# PWM_CONTROLLER.net
KiCad netlist of a schematic drawn in Altium Designer
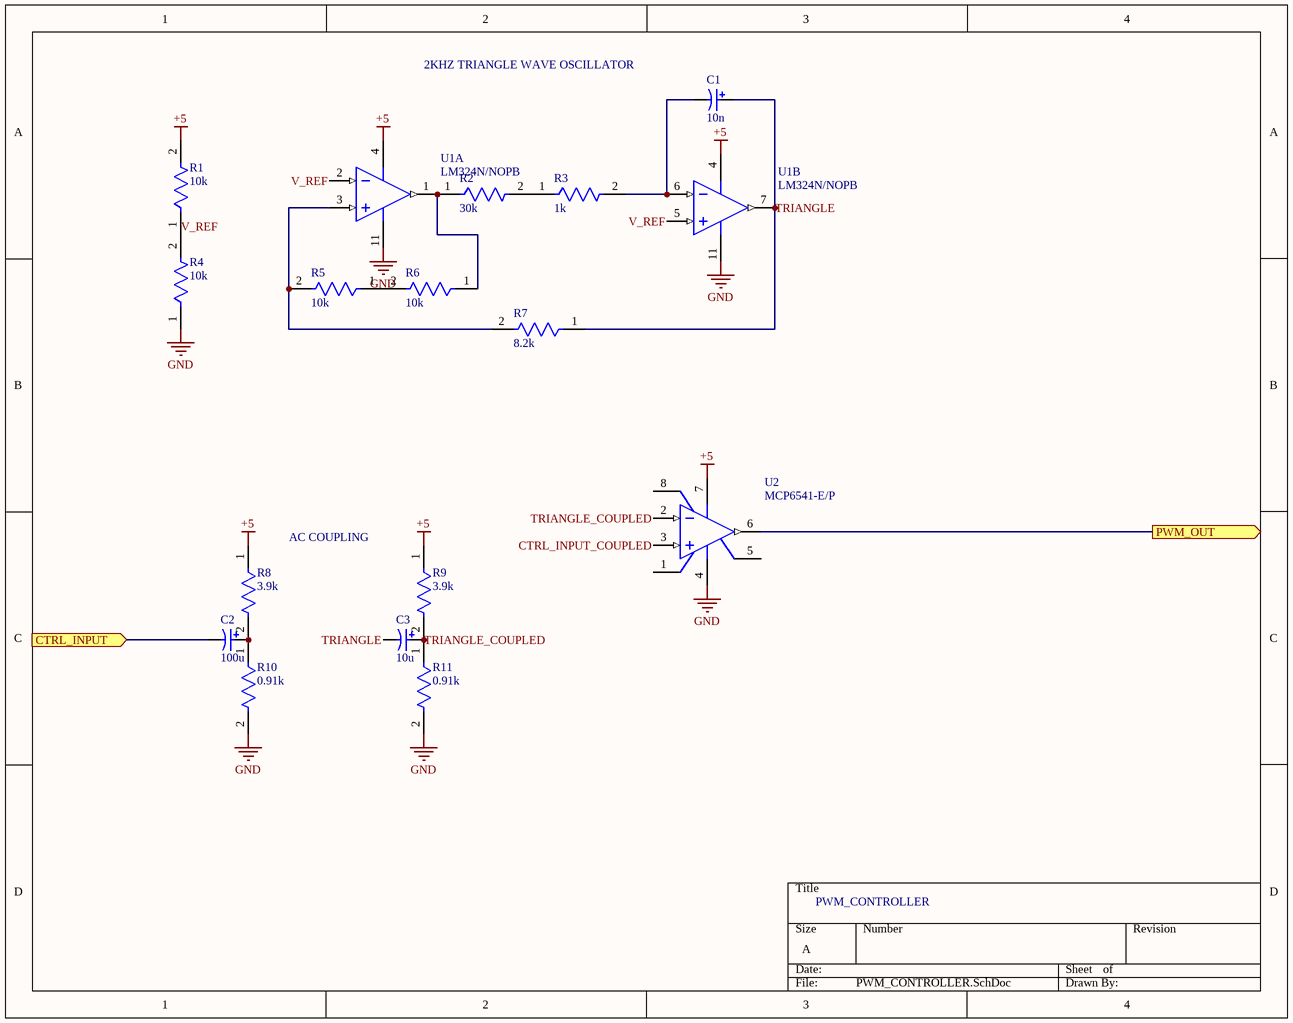
[diagram p0: PWM_CONTROLLER.SchDoc]

(export (version "E")
  (design (tool "Eeschema 10.0.6"))
  (components
    (comp (ref "C1")
      (value "10n")
      (footprint "PNSC-ECA-1VM221-2")
      (description "Aluminum Electrolytic Capacitor, 220 uF, +/- 20%, 35 V, -40 to 85 degC, 2-Pin THD, RoHS, Bulk")
      (fields (field (name "MANUFACTURER") "Panasonic"))
      (libsource (lib "Altium Content Vault") (part "CAP-P-2"))
    )
    (comp (ref "C2")
      (value "100u")
      (footprint "PNSC-ECA-1VM221-2")
      (description "Aluminum Electrolytic Capacitor, 220 uF, +/- 20%, 35 V, -40 to 85 degC, 2-Pin THD, RoHS, Bulk")
      (fields (field (name "MANUFACTURER") "Panasonic"))
      (libsource (lib "Altium Content Vault") (part "CAP-P-2"))
    )
    (comp (ref "C3")
      (value "10u")
      (footprint "PNSC-ECA-1VM221-2")
      (description "Aluminum Electrolytic Capacitor, 220 uF, +/- 20%, 35 V, -40 to 85 degC, 2-Pin THD, RoHS, Bulk")
      (fields (field (name "MANUFACTURER") "Panasonic"))
      (libsource (lib "Altium Content Vault") (part "CAP-P-2"))
    )
    (comp (ref "R1")
      (value "10k")
      (footprint "FP-CF18-MFG")
      (description "RES 2.2K OHM 1/8W 5% CF AXIAL")
      (fields
        (field (name "OCTOPART") "https://octopart.com/cf18jt2k20-stackpole+electronics-19205714")
        (field (name "TOLERANCE") "5%")
      )
      (libsource (lib "Altium Content Vault") (part "1029c3af85768c4190bb7ad29bc67b5"))
    )
    (comp (ref "R2")
      (value "30k")
      (footprint "FP-CF18-MFG")
      (description "RES 2.2K OHM 1/8W 5% CF AXIAL")
      (fields
        (field (name "OCTOPART") "https://octopart.com/cf18jt2k20-stackpole+electronics-19205714")
        (field (name "TOLERANCE") "5%")
      )
      (libsource (lib "Altium Content Vault") (part "1029c3af85768c4190bb7ad29bc67b5"))
    )
    (comp (ref "R3")
      (value "1k")
      (footprint "FP-CF18-MFG")
      (description "RES 2.2K OHM 1/8W 5% CF AXIAL")
      (fields
        (field (name "OCTOPART") "https://octopart.com/cf18jt2k20-stackpole+electronics-19205714")
        (field (name "TOLERANCE") "5%")
      )
      (libsource (lib "Altium Content Vault") (part "1029c3af85768c4190bb7ad29bc67b5"))
    )
    (comp (ref "R4")
      (value "10k")
      (footprint "FP-CF18-MFG")
      (description "RES 2.2K OHM 1/8W 5% CF AXIAL")
      (fields
        (field (name "OCTOPART") "https://octopart.com/cf18jt2k20-stackpole+electronics-19205714")
        (field (name "TOLERANCE") "5%")
      )
      (libsource (lib "Altium Content Vault") (part "1029c3af85768c4190bb7ad29bc67b5"))
    )
    (comp (ref "R5")
      (value "10k")
      (footprint "FP-CF18-MFG")
      (description "RES 2.2K OHM 1/8W 5% CF AXIAL")
      (fields
        (field (name "OCTOPART") "https://octopart.com/cf18jt2k20-stackpole+electronics-19205714")
        (field (name "TOLERANCE") "5%")
      )
      (libsource (lib "Altium Content Vault") (part "1029c3af85768c4190bb7ad29bc67b5"))
    )
    (comp (ref "R6")
      (value "10k")
      (footprint "FP-CF18-MFG")
      (description "RES 2.2K OHM 1/8W 5% CF AXIAL")
      (fields
        (field (name "OCTOPART") "https://octopart.com/cf18jt2k20-stackpole+electronics-19205714")
        (field (name "TOLERANCE") "5%")
      )
      (libsource (lib "Altium Content Vault") (part "1029c3af85768c4190bb7ad29bc67b5"))
    )
    (comp (ref "R7")
      (value "8.2k")
      (footprint "FP-CF18-MFG")
      (description "RES 2.2K OHM 1/8W 5% CF AXIAL")
      (fields
        (field (name "OCTOPART") "https://octopart.com/cf18jt2k20-stackpole+electronics-19205714")
        (field (name "TOLERANCE") "5%")
      )
      (libsource (lib "Altium Content Vault") (part "1029c3af85768c4190bb7ad29bc67b5"))
    )
    (comp (ref "R8")
      (value "3.9k")
      (footprint "FP-CF18-MFG")
      (description "RES 2.2K OHM 1/8W 5% CF AXIAL")
      (fields
        (field (name "OCTOPART") "https://octopart.com/cf18jt2k20-stackpole+electronics-19205714")
        (field (name "TOLERANCE") "5%")
      )
      (libsource (lib "Altium Content Vault") (part "1029c3af85768c4190bb7ad29bc67b5"))
    )
    (comp (ref "R9")
      (value "3.9k")
      (footprint "FP-CF18-MFG")
      (description "RES 2.2K OHM 1/8W 5% CF AXIAL")
      (fields
        (field (name "OCTOPART") "https://octopart.com/cf18jt2k20-stackpole+electronics-19205714")
        (field (name "TOLERANCE") "5%")
      )
      (libsource (lib "Altium Content Vault") (part "1029c3af85768c4190bb7ad29bc67b5"))
    )
    (comp (ref "R10")
      (value "0.91k")
      (footprint "FP-CF18-MFG")
      (description "RES 2.2K OHM 1/8W 5% CF AXIAL")
      (fields
        (field (name "OCTOPART") "https://octopart.com/cf18jt2k20-stackpole+electronics-19205714")
        (field (name "TOLERANCE") "5%")
      )
      (libsource (lib "Altium Content Vault") (part "1029c3af85768c4190bb7ad29bc67b5"))
    )
    (comp (ref "R11")
      (value "0.91k")
      (footprint "FP-CF18-MFG")
      (description "RES 2.2K OHM 1/8W 5% CF AXIAL")
      (fields
        (field (name "OCTOPART") "https://octopart.com/cf18jt2k20-stackpole+electronics-19205714")
        (field (name "TOLERANCE") "5%")
      )
      (libsource (lib "Altium Content Vault") (part "1029c3af85768c4190bb7ad29bc67b5"))
    )
    (comp (ref "U1")
      (value "LM324N/NOPB")
      (footprint "NFF0014A")
      (description "Low Power Quad Operational Amplifier, 14-pin MDIP, Pb-Free")
      (fields (field (name "MANUFACTURER") "Texas Instruments"))
      (libsource (lib "Altium Content Vault") (part "AMP-OPA-LM124-14"))
    )
    (comp (ref "U2")
      (value "MCP6541-E/P")
      (footprint "PDIP300-P8")
      (description "Push-Pull Output Sub-Microamp Comparator, 8-Pin PDIP, Extended Temperature")
      (libsource (lib "Altium Content Vault") (part "AMP-OPA-MCP6541-IL8"))
    )
  )
  (nets
    (net (code "1") (name "+5") (class "Default")
      (node (ref "R1") (pin "2") (pinfunction "2_2") (pintype "passive"))
      (node (ref "R8") (pin "1") (pinfunction "1_1") (pintype "passive"))
      (node (ref "R9") (pin "1") (pinfunction "1_1") (pintype "passive"))
      (node (ref "U1") (pin "4") (pinfunction "V+_4") (pintype "power_in"))
      (node (ref "U2") (pin "7") (pinfunction "VDD_7") (pintype "power_in"))
    )
    (net (code "2") (name "/CTRL_INPUT") (class "Default")
      (node (ref "C2") (pin "2") (pinfunction "2_2") (pintype "passive"))
    )
    (net (code "3") (name "/CTRL_INPUT_COUPLED") (class "Default")
      (node (ref "U2") (pin "3") (pinfunction "VIN+_3") (pintype "input"))
    )
    (net (code "4") (name "/PWM_OUT") (class "Default")
      (node (ref "U2") (pin "6") (pinfunction "OUT_6") (pintype "output"))
    )
    (net (code "5") (name "/TRIANGLE") (class "Default")
      (node (ref "C1") (pin "1") (pinfunction "1_1") (pintype "passive"))
      (node (ref "C3") (pin "2") (pinfunction "2_2") (pintype "passive"))
      (node (ref "R7") (pin "1") (pinfunction "1_1") (pintype "passive"))
      (node (ref "U1") (pin "7") (pinfunction "OUT2_7") (pintype "output"))
    )
    (net (code "6") (name "/TRIANGLE_COUPLED") (class "Default")
      (node (ref "C3") (pin "1") (pinfunction "1_1") (pintype "passive"))
      (node (ref "R11") (pin "1") (pinfunction "1_1") (pintype "passive"))
      (node (ref "R9") (pin "2") (pinfunction "2_2") (pintype "passive"))
      (node (ref "U2") (pin "2") (pinfunction "VIN-_2") (pintype "input"))
    )
    (net (code "7") (name "/V_REF") (class "Default")
      (node (ref "R1") (pin "1") (pinfunction "1_1") (pintype "passive"))
      (node (ref "R4") (pin "2") (pinfunction "2_2") (pintype "passive"))
      (node (ref "U1") (pin "2") (pinfunction "IN1-_2") (pintype "input"))
      (node (ref "U1") (pin "5") (pinfunction "IN2+_5") (pintype "input"))
    )
    (net (code "8") (name "GND") (class "Default")
      (node (ref "R10") (pin "2") (pinfunction "2_2") (pintype "passive"))
      (node (ref "R11") (pin "2") (pinfunction "2_2") (pintype "passive"))
      (node (ref "R4") (pin "1") (pinfunction "1_1") (pintype "passive"))
      (node (ref "U1") (pin "11") (pinfunction "GND_11") (pintype "power_in"))
      (node (ref "U2") (pin "4") (pinfunction "VSS_4") (pintype "power_in"))
    )
    (net (code "9") (name "Net-(C2-Pad1)") (class "Default")
      (node (ref "C2") (pin "1") (pinfunction "1_1") (pintype "passive"))
      (node (ref "R10") (pin "1") (pinfunction "1_1") (pintype "passive"))
      (node (ref "R8") (pin "2") (pinfunction "2_2") (pintype "passive"))
    )
    (net (code "10") (name "Net-(R2-Pad2)") (class "Default")
      (node (ref "R2") (pin "2") (pinfunction "2_2") (pintype "passive"))
      (node (ref "R3") (pin "1") (pinfunction "1_1") (pintype "passive"))
    )
    (net (code "11") (name "Net-(R5-Pad1)") (class "Default")
      (node (ref "R5") (pin "1") (pinfunction "1_1") (pintype "passive"))
      (node (ref "R6") (pin "2") (pinfunction "2_2") (pintype "passive"))
    )
    (net (code "12") (name "Net-(U1A-IN1+)") (class "Default")
      (node (ref "R5") (pin "2") (pinfunction "2_2") (pintype "passive"))
      (node (ref "R7") (pin "2") (pinfunction "2_2") (pintype "passive"))
      (node (ref "U1") (pin "3") (pinfunction "IN1+_3") (pintype "input"))
    )
    (net (code "13") (name "Net-(U1A-OUT1)") (class "Default")
      (node (ref "R2") (pin "1") (pinfunction "1_1") (pintype "passive"))
      (node (ref "R6") (pin "1") (pinfunction "1_1") (pintype "passive"))
      (node (ref "U1") (pin "1") (pinfunction "OUT1_1") (pintype "output"))
    )
    (net (code "14") (name "Net-(U1B-IN2-)") (class "Default")
      (node (ref "C1") (pin "2") (pinfunction "2_2") (pintype "passive"))
      (node (ref "R3") (pin "2") (pinfunction "2_2") (pintype "passive"))
      (node (ref "U1") (pin "6") (pinfunction "IN2-_6") (pintype "input"))
    )
    (net (code "15") (name "unconnected-(U2-NC-Pad1)") (class "Default")
      (node (ref "U2") (pin "1") (pinfunction "NC_1") (pintype "passive"))
    )
    (net (code "16") (name "unconnected-(U2-NC-Pad5)") (class "Default")
      (node (ref "U2") (pin "5") (pinfunction "NC_5") (pintype "passive"))
    )
    (net (code "17") (name "unconnected-(U2-NC-Pad8)") (class "Default")
      (node (ref "U2") (pin "8") (pinfunction "NC_8") (pintype "passive"))
    )
  )
)
